# IridiumGpsAntenna.net
KiCad netlist of a schematic drawn in Altium Designer
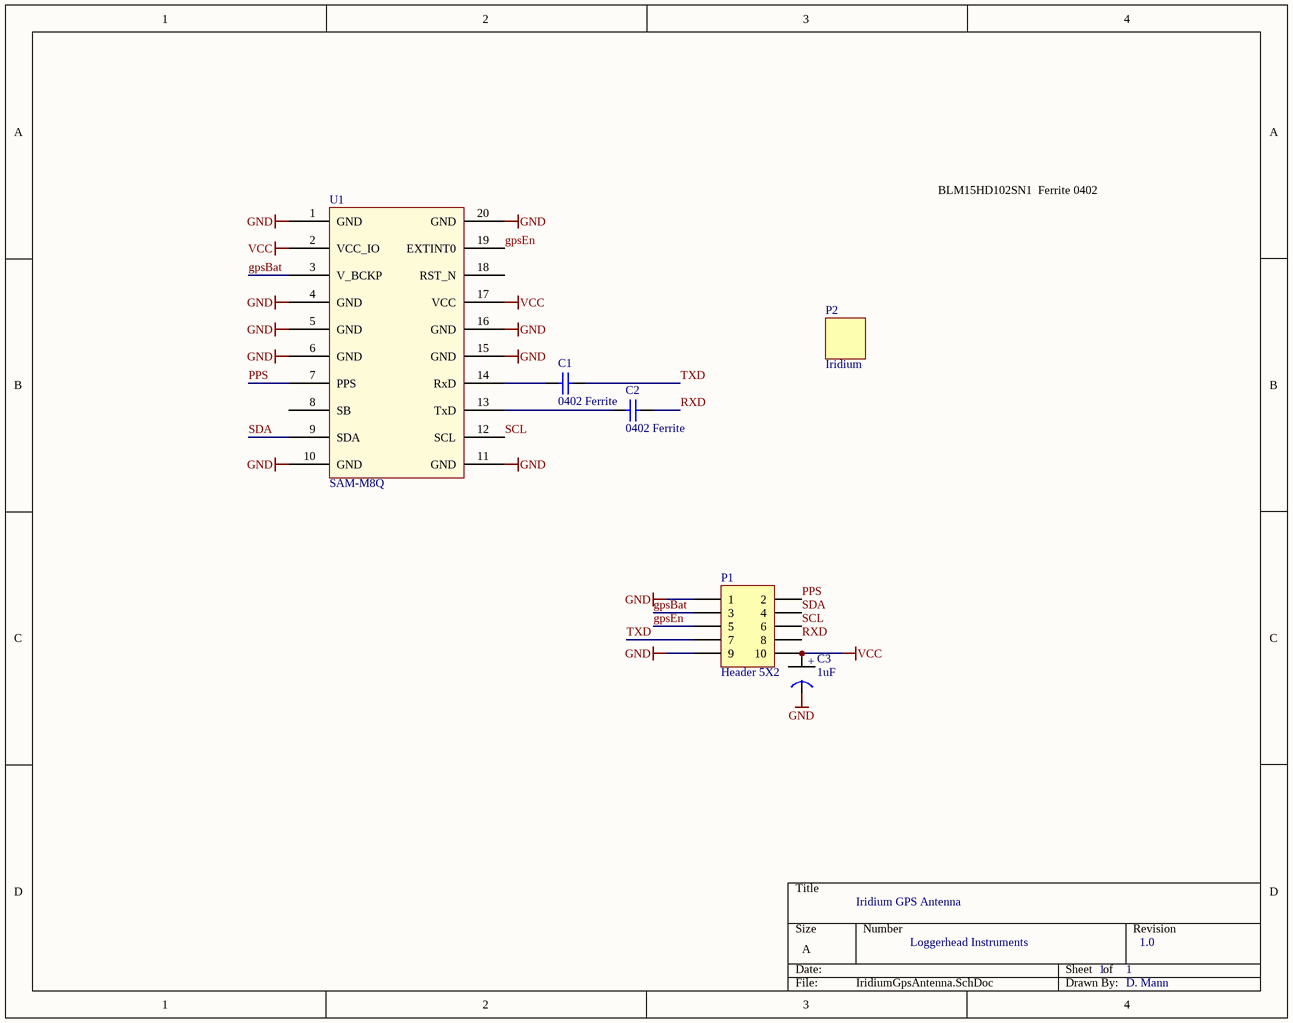
[diagram p0: IridiumGpsAntenna.SchDoc]

(export (version "E")
  (design (tool "Eeschema 10.0.6"))
  (components
    (comp (ref "C1")
      (value "0402 Ferrite")
      (footprint "0402")
      (description "Ceramic Chip Capacitor - Standard")
      (fields (field (name "PUBLISHER") "Altium Limited"))
      (libsource (lib "KEMET Chip Capacitor") (part "C0402"))
    )
    (comp (ref "C2")
      (value "0402 Ferrite")
      (footprint "0402")
      (description "Ceramic Chip Capacitor - Standard")
      (fields (field (name "PUBLISHER") "Altium Limited"))
      (libsource (lib "KEMET Chip Capacitor") (part "C0402"))
    )
    (comp (ref "C3") (value "1uF") (footprint "Tant0805") (libsource (lib "Loggerhead") (part "Tant0805")))
    (comp (ref "P1")
      (value "Header 5X2")
      (footprint "HDR2X5")
      (description "Header, 5-Pin, Dual row")
      (fields (field (name "PUBLISHER") "Altium Limited"))
      (libsource (lib "Miscellaneous Connectors") (part "Header 5X2"))
    )
    (comp (ref "P2")
      (value "Iridium")
      (footprint "Iridium Antenna")
      (libsource (lib "Loggerhead") (part "Iridium Antenna"))
    )
    (comp (ref "U1")
      (value "SAM-M8Q")
      (footprint "GPS SAM-MQ8")
      (libsource (lib "Loggerhead") (part "GPS SAM-M8Q"))
    )
  )
  (nets
    (net (code "1") (name "/PPS") (class "Default")
      (node (ref "P1") (pin "2") (pinfunction "2_2") (pintype "passive"))
      (node (ref "U1") (pin "7") (pinfunction "PPS_7") (pintype "passive"))
    )
    (net (code "2") (name "/RXD") (class "Default")
      (node (ref "C2") (pin "2") (pinfunction "2_2") (pintype "passive"))
      (node (ref "P1") (pin "8") (pinfunction "8_8") (pintype "passive"))
    )
    (net (code "3") (name "/SCL") (class "Default")
      (node (ref "P1") (pin "6") (pinfunction "6_6") (pintype "passive"))
      (node (ref "U1") (pin "12") (pinfunction "SCL_12") (pintype "passive"))
    )
    (net (code "4") (name "/SDA") (class "Default")
      (node (ref "P1") (pin "4") (pinfunction "4_4") (pintype "passive"))
      (node (ref "U1") (pin "9") (pinfunction "SDA_9") (pintype "passive"))
    )
    (net (code "5") (name "/TXD") (class "Default")
      (node (ref "C1") (pin "2") (pinfunction "2_2") (pintype "passive"))
      (node (ref "P1") (pin "7") (pinfunction "7_7") (pintype "passive"))
    )
    (net (code "6") (name "/gpsBat") (class "Default")
      (node (ref "P1") (pin "3") (pinfunction "3_3") (pintype "passive"))
      (node (ref "U1") (pin "3") (pinfunction "V_BCKP_3") (pintype "passive"))
    )
    (net (code "7") (name "/gpsEn") (class "Default")
      (node (ref "P1") (pin "5") (pinfunction "5_5") (pintype "passive"))
      (node (ref "U1") (pin "19") (pinfunction "EXTINT0_19") (pintype "passive"))
    )
    (net (code "8") (name "GND") (class "Default")
      (node (ref "C3") (pin "1") (pinfunction "GND_1") (pintype "passive"))
      (node (ref "P1") (pin "1") (pinfunction "1_1") (pintype "passive"))
      (node (ref "P1") (pin "9") (pinfunction "9_9") (pintype "passive"))
      (node (ref "U1") (pin "1") (pinfunction "GND_1") (pintype "passive"))
      (node (ref "U1") (pin "10") (pinfunction "GND_10") (pintype "passive"))
      (node (ref "U1") (pin "11") (pinfunction "GND_11") (pintype "passive"))
      (node (ref "U1") (pin "15") (pinfunction "GND_15") (pintype "passive"))
      (node (ref "U1") (pin "16") (pinfunction "GND_16") (pintype "passive"))
      (node (ref "U1") (pin "20") (pinfunction "GND_20") (pintype "passive"))
      (node (ref "U1") (pin "4") (pinfunction "GND_4") (pintype "passive"))
      (node (ref "U1") (pin "5") (pinfunction "GND_5") (pintype "passive"))
      (node (ref "U1") (pin "6") (pinfunction "GND_6") (pintype "passive"))
    )
    (net (code "9") (name "Net-(U1-RxD)") (class "Default")
      (node (ref "C1") (pin "1") (pinfunction "1_1") (pintype "passive"))
      (node (ref "U1") (pin "14") (pinfunction "RxD_14") (pintype "passive"))
    )
    (net (code "10") (name "Net-(U1-TxD)") (class "Default")
      (node (ref "C2") (pin "1") (pinfunction "1_1") (pintype "passive"))
      (node (ref "U1") (pin "13") (pinfunction "TxD_13") (pintype "passive"))
    )
    (net (code "11") (name "VCC") (class "Default")
      (node (ref "C3") (pin "2") (pinfunction "+_2") (pintype "passive"))
      (node (ref "P1") (pin "10") (pinfunction "10_10") (pintype "passive"))
      (node (ref "U1") (pin "17") (pinfunction "VCC_17") (pintype "passive"))
      (node (ref "U1") (pin "2") (pinfunction "VCC_IO_2") (pintype "passive"))
    )
    (net (code "12") (name "unconnected-(U1-RST_N-Pad18)") (class "Default")
      (node (ref "U1") (pin "18") (pinfunction "RST_N_18") (pintype "passive"))
    )
    (net (code "13") (name "unconnected-(U1-SB-Pad8)") (class "Default")
      (node (ref "U1") (pin "8") (pinfunction "SB_8") (pintype "passive"))
    )
  )
)
